# KORUZA_RPi_shield.net
KiCad netlist of a schematic drawn in Altium Designer
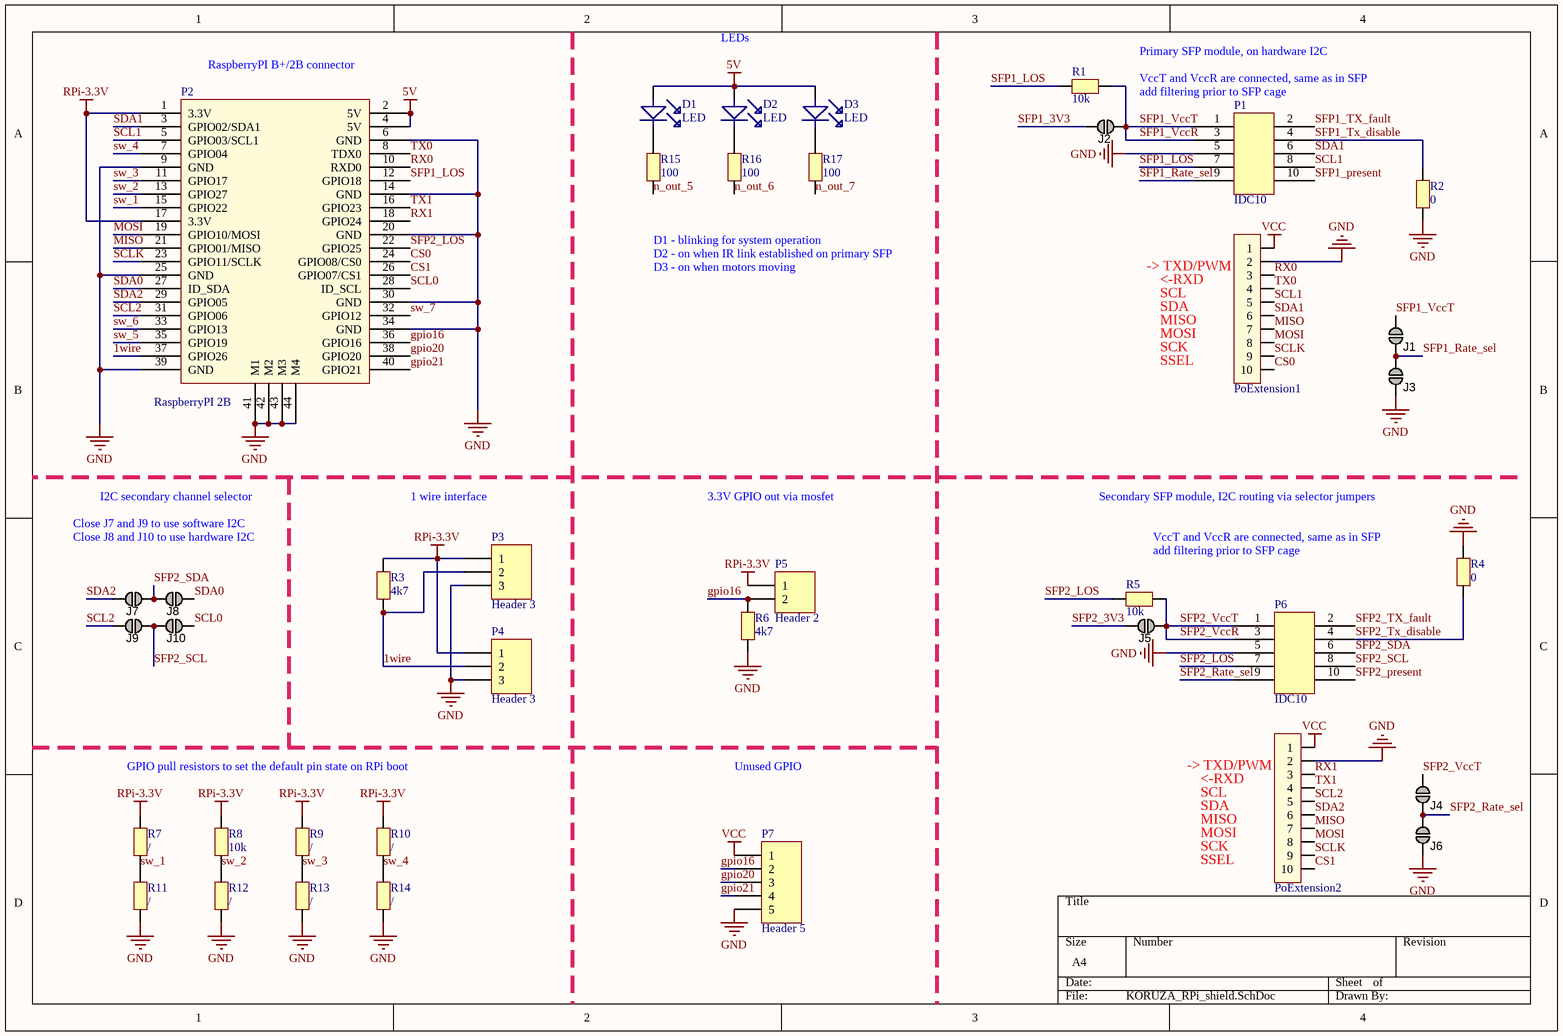
[diagram p0: KORUZA_RPi_shield.SchDoc]

(export (version "E")
  (design (tool "Eeschema 10.0.6"))
  (components
    (comp (ref "D1")
      (value "LED")
      (footprint "1206/0805 diode")
      (description "LED diode")
      (libsource (lib "GeneralComponents") (part "LED"))
    )
    (comp (ref "D2")
      (value "LED")
      (footprint "1206/0805 diode")
      (description "LED diode")
      (libsource (lib "GeneralComponents") (part "LED"))
    )
    (comp (ref "D3")
      (value "LED")
      (footprint "1206/0805 diode")
      (description "LED diode")
      (libsource (lib "GeneralComponents") (part "LED"))
    )
    (comp (ref "J1")
      (value "Jumper")
      (footprint "JUMP1")
      (description "SMD jumper")
      (libsource (lib "Misc") (part "JUMP1"))
    )
    (comp (ref "J2")
      (value "Jumper")
      (footprint "JUMP1")
      (description "SMD jumper")
      (libsource (lib "Misc") (part "JUMP1"))
    )
    (comp (ref "J3")
      (value "Jumper")
      (footprint "JUMP1")
      (description "SMD jumper")
      (libsource (lib "Misc") (part "JUMP1"))
    )
    (comp (ref "J4")
      (value "Jumper")
      (footprint "JUMP1")
      (description "SMD jumper")
      (libsource (lib "Misc") (part "JUMP1"))
    )
    (comp (ref "J5")
      (value "Jumper")
      (footprint "JUMP1")
      (description "SMD jumper")
      (libsource (lib "Misc") (part "JUMP1"))
    )
    (comp (ref "J6")
      (value "Jumper")
      (footprint "JUMP1")
      (description "SMD jumper")
      (libsource (lib "Misc") (part "JUMP1"))
    )
    (comp (ref "J7")
      (value "Jumper")
      (footprint "JUMP1")
      (description "SMD jumper")
      (libsource (lib "Misc") (part "JUMP1"))
    )
    (comp (ref "J8")
      (value "Jumper")
      (footprint "JUMP1")
      (description "SMD jumper")
      (libsource (lib "Misc") (part "JUMP1"))
    )
    (comp (ref "J9")
      (value "Jumper")
      (footprint "JUMP1")
      (description "SMD jumper")
      (libsource (lib "Misc") (part "JUMP1"))
    )
    (comp (ref "J10")
      (value "Jumper")
      (footprint "JUMP1")
      (description "SMD jumper")
      (libsource (lib "Misc") (part "JUMP1"))
    )
    (comp (ref "P1")
      (value "IDC10")
      (footprint "IDC10")
      (description "IDC 10pin")
      (libsource (lib "GeneralComponents") (part "IDC10"))
    )
    (comp (ref "P2")
      (value "RaspberryPI 2B")
      (footprint "RaspberryPI_B+")
      (description "RPi2")
      (libsource (lib "GeneralComponents") (part "RaspberryPI 2B"))
    )
    (comp (ref "P3")
      (value "Header 3")
      (footprint "HDR1X3")
      (description "Header, 3-Pin")
      (fields (field (name "PUBLISHER") "Altium Limited"))
      (libsource (lib "Miscellaneous Connectors") (part "Header 3"))
    )
    (comp (ref "P4")
      (value "Header 3")
      (footprint "HDR1X3")
      (description "Header, 3-Pin")
      (fields (field (name "PUBLISHER") "Altium Limited"))
      (libsource (lib "Miscellaneous Connectors") (part "Header 3"))
    )
    (comp (ref "P5")
      (value "Header 2")
      (footprint "HDR1X2")
      (description "Header, 2-Pin")
      (fields (field (name "PUBLISHER") "Altium Limited"))
      (libsource (lib "Miscellaneous Connectors") (part "Header 2"))
    )
    (comp (ref "P6")
      (value "IDC10")
      (footprint "IDC10")
      (description "IDC 10pin")
      (libsource (lib "GeneralComponents") (part "IDC10"))
    )
    (comp (ref "P7")
      (value "Header 5")
      (footprint "HDR1X5")
      (description "Header, 5-Pin")
      (fields (field (name "PUBLISHER") "Altium Limited"))
      (libsource (lib "Miscellaneous Connectors") (part "Header 5"))
    )
    (comp (ref "PoExtension1")
      (value "~")
      (footprint "BorisMicroMatch:8-188275-0")
      (description "Micro-Match female PCB connector 10 Positions THT")
      (libsource (lib "BorisMicroMatch") (part "1-215079-0"))
    )
    (comp (ref "PoExtension2")
      (value "~")
      (footprint "BorisMicroMatch:8-188275-0")
      (description "Micro-Match female PCB connector 10 Positions THT")
      (libsource (lib "BorisMicroMatch") (part "1-215079-0"))
    )
    (comp (ref "R1")
      (value "10k")
      (footprint "RESC2012X06N")
      (description "Resistor 0805 smd")
      (libsource (lib "") (part "Resistor_1"))
    )
    (comp (ref "R2")
      (value "0")
      (footprint "RESC2012X06N")
      (description "Resistor 0805 smd")
      (libsource (lib "GeneralComponents") (part "Resistor"))
    )
    (comp (ref "R3")
      (value "4k7")
      (footprint "RESC2012X06N")
      (description "Resistor 0805 smd")
      (libsource (lib "GeneralComponents") (part "Resistor"))
    )
    (comp (ref "R4")
      (value "0")
      (footprint "RESC2012X06N")
      (description "Resistor 0805 smd")
      (libsource (lib "GeneralComponents") (part "Resistor"))
    )
    (comp (ref "R5")
      (value "10k")
      (footprint "RESC2012X06N")
      (description "Resistor 0805 smd")
      (libsource (lib "") (part "Resistor_1"))
    )
    (comp (ref "R6")
      (value "4k7")
      (footprint "RESC2012X06N")
      (description "Resistor 0805 smd")
      (libsource (lib "GeneralComponents") (part "Resistor"))
    )
    (comp (ref "R7")
      (value "/")
      (footprint "RESC2012X06N")
      (description "Resistor 0805 smd")
      (libsource (lib "GeneralComponents") (part "Resistor"))
    )
    (comp (ref "R8")
      (value "10k")
      (footprint "RESC2012X06N")
      (description "Resistor 0805 smd")
      (libsource (lib "GeneralComponents") (part "Resistor"))
    )
    (comp (ref "R9")
      (value "/")
      (footprint "RESC2012X06N")
      (description "Resistor 0805 smd")
      (libsource (lib "GeneralComponents") (part "Resistor"))
    )
    (comp (ref "R10")
      (value "/")
      (footprint "RESC2012X06N")
      (description "Resistor 0805 smd")
      (libsource (lib "GeneralComponents") (part "Resistor"))
    )
    (comp (ref "R11")
      (value "/")
      (footprint "RESC2012X06N")
      (description "Resistor 0805 smd")
      (libsource (lib "GeneralComponents") (part "Resistor"))
    )
    (comp (ref "R12")
      (value "/")
      (footprint "RESC2012X06N")
      (description "Resistor 0805 smd")
      (libsource (lib "GeneralComponents") (part "Resistor"))
    )
    (comp (ref "R13")
      (value "/")
      (footprint "RESC2012X06N")
      (description "Resistor 0805 smd")
      (libsource (lib "GeneralComponents") (part "Resistor"))
    )
    (comp (ref "R14")
      (value "/")
      (footprint "RESC2012X06N")
      (description "Resistor 0805 smd")
      (libsource (lib "GeneralComponents") (part "Resistor"))
    )
    (comp (ref "R15")
      (value "100")
      (footprint "RESC2012X06N")
      (description "Resistor 0805 smd")
      (libsource (lib "GeneralComponents") (part "Resistor"))
    )
    (comp (ref "R16")
      (value "100")
      (footprint "RESC2012X06N")
      (description "Resistor 0805 smd")
      (libsource (lib "GeneralComponents") (part "Resistor"))
    )
    (comp (ref "R17")
      (value "100")
      (footprint "RESC2012X06N")
      (description "Resistor 0805 smd")
      (libsource (lib "GeneralComponents") (part "Resistor"))
    )
  )
  (nets
    (net (code "1") (name "/1wire") (class "Default")
      (node (ref "P2") (pin "37") (pinfunction "GPIO26_37") (pintype "passive"))
      (node (ref "P3") (pin "2") (pinfunction "2_2") (pintype "passive"))
      (node (ref "P4") (pin "2") (pinfunction "2_2") (pintype "passive"))
      (node (ref "R3") (pin "1") (pinfunction "1_1") (pintype "passive"))
    )
    (net (code "2") (name "/CS0") (class "Default")
      (node (ref "P2") (pin "24") (pinfunction "GPIO08/CS0_24") (pintype "passive"))
      (node (ref "PoExtension1") (pin "10") (pinfunction "10_10") (pintype "passive"))
    )
    (net (code "3") (name "/CS1") (class "Default")
      (node (ref "P2") (pin "26") (pinfunction "GPIO07/CS1_26") (pintype "passive"))
      (node (ref "PoExtension2") (pin "10") (pinfunction "10_10") (pintype "passive"))
    )
    (net (code "4") (name "/MISO") (class "Default")
      (node (ref "P2") (pin "21") (pinfunction "GPIO01/MISO_21") (pintype "passive"))
      (node (ref "PoExtension1") (pin "7") (pinfunction "7_7") (pintype "passive"))
      (node (ref "PoExtension2") (pin "7") (pinfunction "7_7") (pintype "passive"))
    )
    (net (code "5") (name "/MOSI") (class "Default")
      (node (ref "P2") (pin "19") (pinfunction "GPIO10/MOSI_19") (pintype "passive"))
      (node (ref "PoExtension1") (pin "8") (pinfunction "8_8") (pintype "passive"))
      (node (ref "PoExtension2") (pin "8") (pinfunction "8_8") (pintype "passive"))
    )
    (net (code "6") (name "/RX0") (class "Default")
      (node (ref "P2") (pin "10") (pinfunction "RXD0_10") (pintype "passive"))
      (node (ref "PoExtension1") (pin "3") (pinfunction "3_3") (pintype "passive"))
    )
    (net (code "7") (name "/RX1") (class "Default")
      (node (ref "P2") (pin "18") (pinfunction "GPIO24_18") (pintype "passive"))
      (node (ref "PoExtension2") (pin "3") (pinfunction "3_3") (pintype "passive"))
    )
    (net (code "8") (name "/SCL0") (class "Default")
      (node (ref "J10") (pin "2") (pintype "passive"))
      (node (ref "P2") (pin "28") (pinfunction "ID_SCL_28") (pintype "passive"))
    )
    (net (code "9") (name "/SCL1") (class "Default")
      (node (ref "P1") (pin "8") (pinfunction "8_8") (pintype "passive"))
      (node (ref "P2") (pin "5") (pinfunction "GPIO03/SCL1_5") (pintype "passive"))
      (node (ref "PoExtension1") (pin "5") (pinfunction "5_5") (pintype "passive"))
    )
    (net (code "10") (name "/SCL2") (class "Default")
      (node (ref "J9") (pin "1") (pintype "passive"))
      (node (ref "P2") (pin "31") (pinfunction "GPIO06_31") (pintype "passive"))
      (node (ref "PoExtension2") (pin "5") (pinfunction "5_5") (pintype "passive"))
    )
    (net (code "11") (name "/SCLK") (class "Default")
      (node (ref "P2") (pin "23") (pinfunction "GPIO11/SCLK_23") (pintype "passive"))
      (node (ref "PoExtension1") (pin "9") (pinfunction "9_9") (pintype "passive"))
      (node (ref "PoExtension2") (pin "9") (pinfunction "9_9") (pintype "passive"))
    )
    (net (code "12") (name "/SDA0") (class "Default")
      (node (ref "J8") (pin "2") (pintype "passive"))
      (node (ref "P2") (pin "27") (pinfunction "ID_SDA_27") (pintype "passive"))
    )
    (net (code "13") (name "/SDA1") (class "Default")
      (node (ref "P1") (pin "6") (pinfunction "6_6") (pintype "passive"))
      (node (ref "P2") (pin "3") (pinfunction "GPIO02/SDA1_3") (pintype "passive"))
      (node (ref "PoExtension1") (pin "6") (pinfunction "6_6") (pintype "passive"))
    )
    (net (code "14") (name "/SDA2") (class "Default")
      (node (ref "J7") (pin "1") (pintype "passive"))
      (node (ref "P2") (pin "29") (pinfunction "GPIO05_29") (pintype "passive"))
      (node (ref "PoExtension2") (pin "6") (pinfunction "6_6") (pintype "passive"))
    )
    (net (code "15") (name "/SFP1_3V3") (class "Default") (node (ref "J2") (pin "1") (pintype "passive")))
    (net (code "16") (name "/SFP1_LOS") (class "Default")
      (node (ref "P1") (pin "7") (pinfunction "7_7") (pintype "passive"))
      (node (ref "P2") (pin "12") (pinfunction "GPIO18_12") (pintype "passive"))
      (node (ref "R1") (pin "2") (pinfunction "2_2") (pintype "passive"))
    )
    (net (code "17") (name "/SFP1_Rate_sel") (class "Default")
      (node (ref "J1") (pin "1") (pintype "passive"))
      (node (ref "J3") (pin "2") (pintype "passive"))
      (node (ref "P1") (pin "9") (pinfunction "9_9") (pintype "passive"))
    )
    (net (code "18") (name "/SFP1_TX_fault") (class "Default")
      (node (ref "P1") (pin "2") (pinfunction "2_2") (pintype "passive"))
    )
    (net (code "19") (name "/SFP1_Tx_disable") (class "Default")
      (node (ref "P1") (pin "4") (pinfunction "4_4") (pintype "passive"))
      (node (ref "R2") (pin "2") (pinfunction "2_2") (pintype "passive"))
    )
    (net (code "20") (name "/SFP1_VccR") (class "Default")
      (node (ref "J1") (pin "2") (pintype "passive"))
      (node (ref "J2") (pin "2") (pintype "passive"))
      (node (ref "P1") (pin "1") (pinfunction "A_1") (pintype "passive"))
      (node (ref "P1") (pin "3") (pinfunction "3_3") (pintype "passive"))
      (node (ref "R1") (pin "1") (pinfunction "1_1") (pintype "passive"))
    )
    (net (code "21") (name "/SFP1_present") (class "Default")
      (node (ref "P1") (pin "10") (pinfunction "10_10") (pintype "passive"))
    )
    (net (code "22") (name "/SFP2_3V3") (class "Default") (node (ref "J5") (pin "1") (pintype "passive")))
    (net (code "23") (name "/SFP2_LOS") (class "Default")
      (node (ref "P2") (pin "22") (pinfunction "GPIO25_22") (pintype "passive"))
      (node (ref "P6") (pin "7") (pinfunction "7_7") (pintype "passive"))
      (node (ref "R5") (pin "2") (pinfunction "2_2") (pintype "passive"))
    )
    (net (code "24") (name "/SFP2_Rate_sel") (class "Default")
      (node (ref "J4") (pin "1") (pintype "passive"))
      (node (ref "J6") (pin "2") (pintype "passive"))
      (node (ref "P6") (pin "9") (pinfunction "9_9") (pintype "passive"))
    )
    (net (code "25") (name "/SFP2_SCL") (class "Default")
      (node (ref "J10") (pin "1") (pintype "passive"))
      (node (ref "J9") (pin "2") (pintype "passive"))
      (node (ref "P6") (pin "8") (pinfunction "8_8") (pintype "passive"))
    )
    (net (code "26") (name "/SFP2_SDA") (class "Default")
      (node (ref "J7") (pin "2") (pintype "passive"))
      (node (ref "J8") (pin "1") (pintype "passive"))
      (node (ref "P6") (pin "6") (pinfunction "6_6") (pintype "passive"))
    )
    (net (code "27") (name "/SFP2_TX_fault") (class "Default")
      (node (ref "P6") (pin "2") (pinfunction "2_2") (pintype "passive"))
    )
    (net (code "28") (name "/SFP2_Tx_disable") (class "Default")
      (node (ref "P6") (pin "4") (pinfunction "4_4") (pintype "passive"))
      (node (ref "R4") (pin "1") (pinfunction "1_1") (pintype "passive"))
    )
    (net (code "29") (name "/SFP2_VccR") (class "Default")
      (node (ref "J4") (pin "2") (pintype "passive"))
      (node (ref "J5") (pin "2") (pintype "passive"))
      (node (ref "P6") (pin "1") (pinfunction "A_1") (pintype "passive"))
      (node (ref "P6") (pin "3") (pinfunction "3_3") (pintype "passive"))
      (node (ref "R5") (pin "1") (pinfunction "1_1") (pintype "passive"))
    )
    (net (code "30") (name "/SFP2_present") (class "Default")
      (node (ref "P6") (pin "10") (pinfunction "10_10") (pintype "passive"))
    )
    (net (code "31") (name "/TX0") (class "Default")
      (node (ref "P2") (pin "8") (pinfunction "TDX0_8") (pintype "passive"))
      (node (ref "PoExtension1") (pin "4") (pinfunction "4_4") (pintype "passive"))
    )
    (net (code "32") (name "/TX1") (class "Default")
      (node (ref "P2") (pin "16") (pinfunction "GPIO23_16") (pintype "passive"))
      (node (ref "PoExtension2") (pin "4") (pinfunction "4_4") (pintype "passive"))
    )
    (net (code "33") (name "/gpio16") (class "Default")
      (node (ref "P2") (pin "36") (pinfunction "GPIO16_36") (pintype "passive"))
      (node (ref "P5") (pin "2") (pinfunction "2_2") (pintype "passive"))
      (node (ref "P7") (pin "2") (pinfunction "2_2") (pintype "passive"))
      (node (ref "R6") (pin "2") (pinfunction "2_2") (pintype "passive"))
    )
    (net (code "34") (name "/gpio20") (class "Default")
      (node (ref "P2") (pin "38") (pinfunction "GPIO20_38") (pintype "passive"))
      (node (ref "P7") (pin "3") (pinfunction "3_3") (pintype "passive"))
    )
    (net (code "35") (name "/gpio21") (class "Default")
      (node (ref "P2") (pin "40") (pinfunction "GPIO21_40") (pintype "passive"))
      (node (ref "P7") (pin "4") (pinfunction "4_4") (pintype "passive"))
    )
    (net (code "36") (name "/n_out_5") (class "Default")
      (node (ref "R15") (pin "1") (pinfunction "1_1") (pintype "passive"))
    )
    (net (code "37") (name "/n_out_6") (class "Default")
      (node (ref "R16") (pin "1") (pinfunction "1_1") (pintype "passive"))
    )
    (net (code "38") (name "/n_out_7") (class "Default")
      (node (ref "R17") (pin "1") (pinfunction "1_1") (pintype "passive"))
    )
    (net (code "39") (name "/sw_1") (class "Default")
      (node (ref "P2") (pin "15") (pinfunction "GPIO22_15") (pintype "passive"))
      (node (ref "R11") (pin "2") (pinfunction "2_2") (pintype "passive"))
      (node (ref "R7") (pin "1") (pinfunction "1_1") (pintype "passive"))
    )
    (net (code "40") (name "/sw_2") (class "Default")
      (node (ref "P2") (pin "13") (pinfunction "GPIO27_13") (pintype "passive"))
      (node (ref "R12") (pin "2") (pinfunction "2_2") (pintype "passive"))
      (node (ref "R8") (pin "1") (pinfunction "1_1") (pintype "passive"))
    )
    (net (code "41") (name "/sw_3") (class "Default")
      (node (ref "P2") (pin "11") (pinfunction "GPIO17_11") (pintype "passive"))
      (node (ref "R13") (pin "2") (pinfunction "2_2") (pintype "passive"))
      (node (ref "R9") (pin "1") (pinfunction "1_1") (pintype "passive"))
    )
    (net (code "42") (name "/sw_4") (class "Default")
      (node (ref "P2") (pin "7") (pinfunction "GPIO04_7") (pintype "passive"))
      (node (ref "R10") (pin "1") (pinfunction "1_1") (pintype "passive"))
      (node (ref "R14") (pin "2") (pinfunction "2_2") (pintype "passive"))
    )
    (net (code "43") (name "/sw_5") (class "Default")
      (node (ref "P2") (pin "35") (pinfunction "GPIO19_35") (pintype "passive"))
    )
    (net (code "44") (name "/sw_6") (class "Default")
      (node (ref "P2") (pin "33") (pinfunction "GPIO13_33") (pintype "passive"))
    )
    (net (code "45") (name "/sw_7") (class "Default")
      (node (ref "P2") (pin "32") (pinfunction "GPIO12_32") (pintype "passive"))
    )
    (net (code "46") (name "5V") (class "Default")
      (node (ref "D1") (pin "1") (pinfunction "1_1") (pintype "passive"))
      (node (ref "D2") (pin "1") (pinfunction "1_1") (pintype "passive"))
      (node (ref "D3") (pin "1") (pinfunction "1_1") (pintype "passive"))
      (node (ref "P2") (pin "2") (pinfunction "5V_2") (pintype "passive"))
      (node (ref "P2") (pin "4") (pinfunction "5V_4") (pintype "passive"))
    )
    (net (code "47") (name "GND") (class "Default")
      (node (ref "J3") (pin "1") (pintype "passive"))
      (node (ref "J6") (pin "1") (pintype "passive"))
      (node (ref "P1") (pin "5") (pinfunction "5_5") (pintype "passive"))
      (node (ref "P2") (pin "14") (pinfunction "GND_14") (pintype "passive"))
      (node (ref "P2") (pin "20") (pinfunction "GND_20") (pintype "passive"))
      (node (ref "P2") (pin "25") (pinfunction "GND_25") (pintype "passive"))
      (node (ref "P2") (pin "30") (pinfunction "GND_30") (pintype "passive"))
      (node (ref "P2") (pin "34") (pinfunction "GND_34") (pintype "passive"))
      (node (ref "P2") (pin "39") (pinfunction "GND_39") (pintype "passive"))
      (node (ref "P2") (pin "41") (pinfunction "M1_41") (pintype "passive"))
      (node (ref "P2") (pin "42") (pinfunction "M2_42") (pintype "passive"))
      (node (ref "P2") (pin "43") (pinfunction "M3_43") (pintype "passive"))
      (node (ref "P2") (pin "44") (pinfunction "M4_44") (pintype "passive"))
      (node (ref "P2") (pin "6") (pinfunction "GND_6") (pintype "passive"))
      (node (ref "P2") (pin "9") (pinfunction "GND_9") (pintype "passive"))
      (node (ref "P3") (pin "3") (pinfunction "3_3") (pintype "passive"))
      (node (ref "P4") (pin "3") (pinfunction "3_3") (pintype "passive"))
      (node (ref "P6") (pin "5") (pinfunction "5_5") (pintype "passive"))
      (node (ref "P7") (pin "5") (pinfunction "5_5") (pintype "passive"))
      (node (ref "PoExtension1") (pin "2") (pinfunction "2_2") (pintype "passive"))
      (node (ref "PoExtension2") (pin "2") (pinfunction "2_2") (pintype "passive"))
      (node (ref "R11") (pin "1") (pinfunction "1_1") (pintype "passive"))
      (node (ref "R12") (pin "1") (pinfunction "1_1") (pintype "passive"))
      (node (ref "R13") (pin "1") (pinfunction "1_1") (pintype "passive"))
      (node (ref "R14") (pin "1") (pinfunction "1_1") (pintype "passive"))
      (node (ref "R2") (pin "1") (pinfunction "1_1") (pintype "passive"))
      (node (ref "R4") (pin "2") (pinfunction "2_2") (pintype "passive"))
      (node (ref "R6") (pin "1") (pinfunction "1_1") (pintype "passive"))
    )
    (net (code "48") (name "Net-(D1-Pad2)") (class "Default")
      (node (ref "D1") (pin "2") (pinfunction "2_2") (pintype "passive"))
      (node (ref "R15") (pin "2") (pinfunction "2_2") (pintype "passive"))
    )
    (net (code "49") (name "Net-(D2-Pad2)") (class "Default")
      (node (ref "D2") (pin "2") (pinfunction "2_2") (pintype "passive"))
      (node (ref "R16") (pin "2") (pinfunction "2_2") (pintype "passive"))
    )
    (net (code "50") (name "Net-(D3-Pad2)") (class "Default")
      (node (ref "D3") (pin "2") (pinfunction "2_2") (pintype "passive"))
      (node (ref "R17") (pin "2") (pinfunction "2_2") (pintype "passive"))
    )
    (net (code "51") (name "RPi-3.3V") (class "Default")
      (node (ref "P2") (pin "1") (pinfunction "3.3V_1") (pintype "passive"))
      (node (ref "P2") (pin "17") (pinfunction "3.3V_17") (pintype "passive"))
      (node (ref "P3") (pin "1") (pinfunction "1_1") (pintype "passive"))
      (node (ref "P4") (pin "1") (pinfunction "1_1") (pintype "passive"))
      (node (ref "P5") (pin "1") (pinfunction "1_1") (pintype "passive"))
      (node (ref "R10") (pin "2") (pinfunction "2_2") (pintype "passive"))
      (node (ref "R3") (pin "2") (pinfunction "2_2") (pintype "passive"))
      (node (ref "R7") (pin "2") (pinfunction "2_2") (pintype "passive"))
      (node (ref "R8") (pin "2") (pinfunction "2_2") (pintype "passive"))
      (node (ref "R9") (pin "2") (pinfunction "2_2") (pintype "passive"))
    )
    (net (code "52") (name "VCC") (class "Default")
      (node (ref "P7") (pin "1") (pinfunction "1_1") (pintype "passive"))
      (node (ref "PoExtension1") (pin "1") (pinfunction "1_1") (pintype "passive"))
      (node (ref "PoExtension2") (pin "1") (pinfunction "1_1") (pintype "passive"))
    )
  )
)
